# Watch1_1.net
KiCad netlist of a schematic drawn in EAGLE
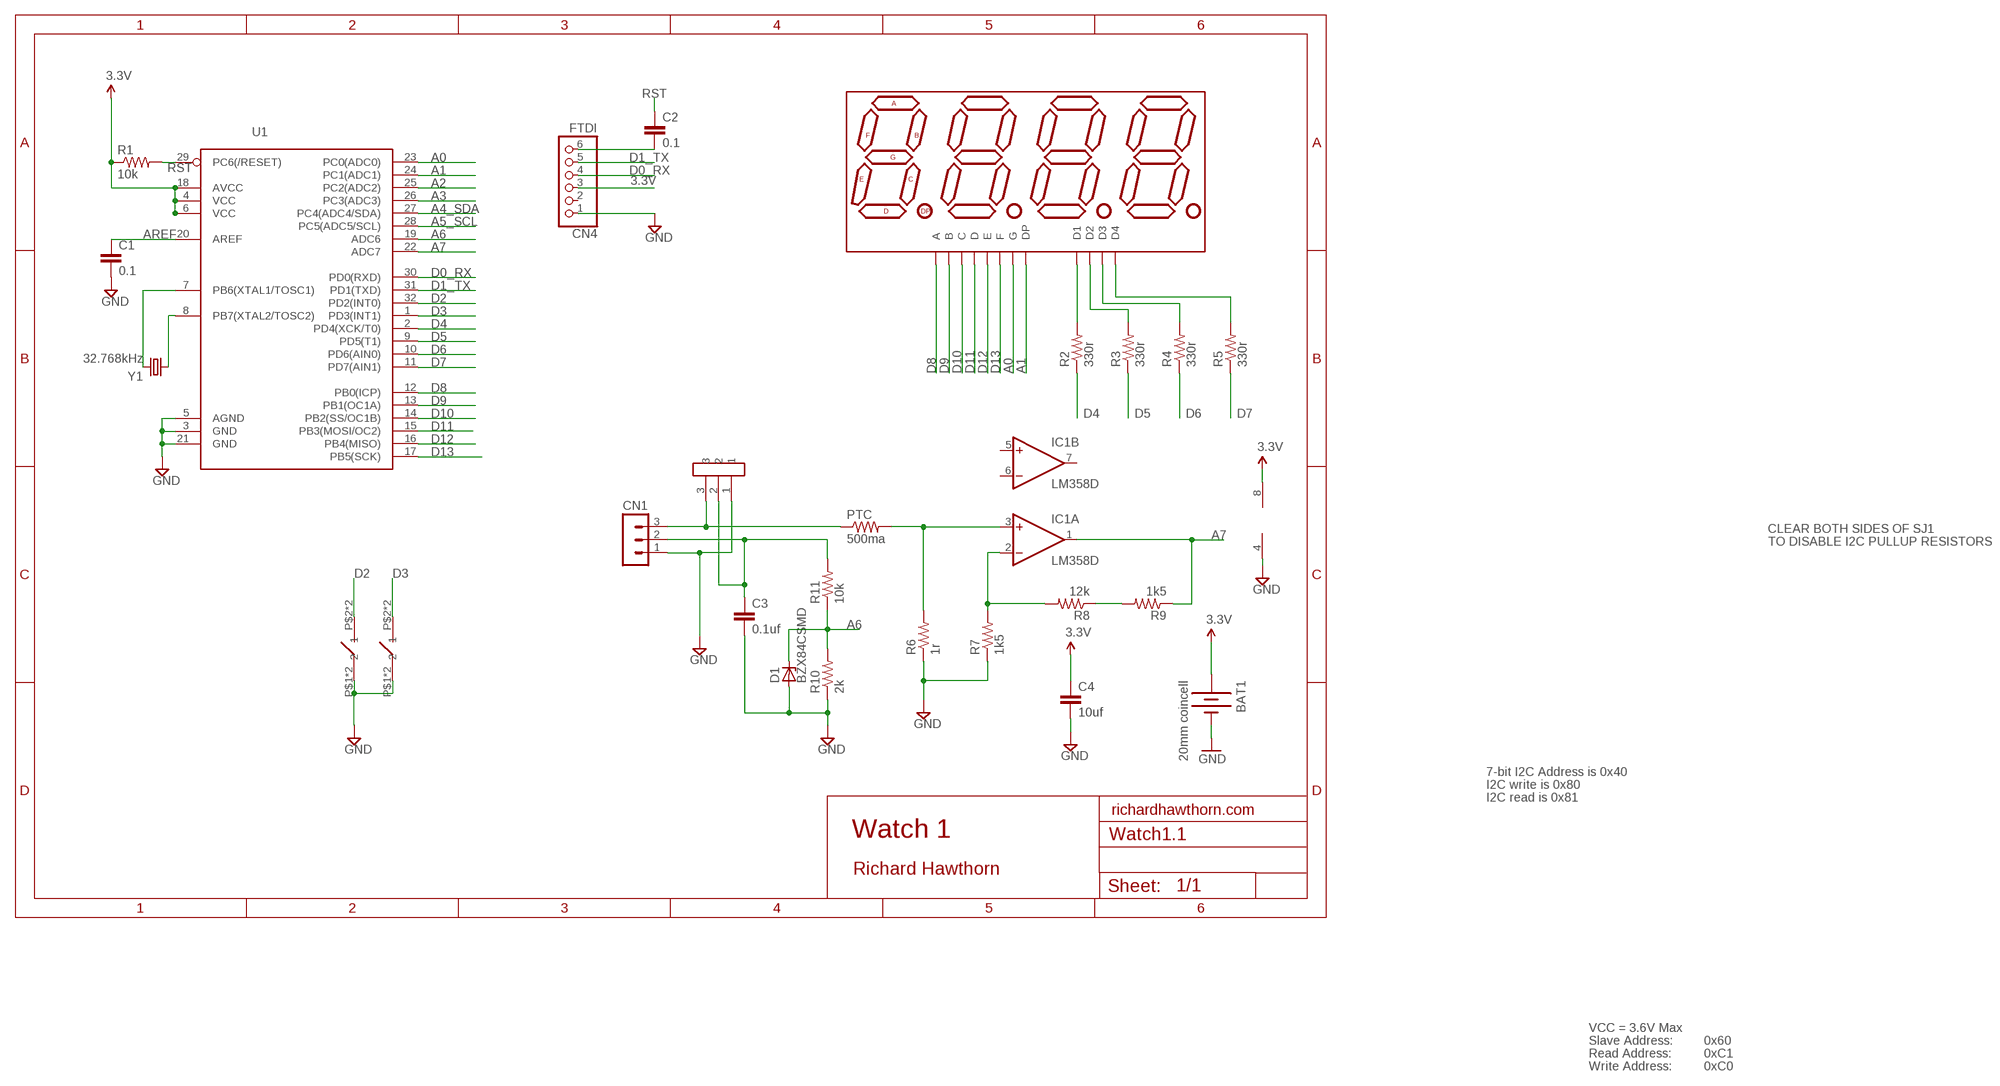
[diagram p0: schematic, sheet 1]

(export (version "E")
  (design (tool "Eeschema 10.0.6"))
  (components
    (comp (ref "BAT1")
      (value "20mm coincell")
      (footprint "eagle-import:BATTCON_20MM_4LEGS_OVERPASTE")
      (libsource (lib "eagle-import") (part "BATTERY20MM_4LEGS_OVERPASTE"))
    )
    (comp (ref "BTN1")
      (value "TURTLE-3PIN")
      (footprint "eagle-import:TURTLE-3PIN")
      (libsource (lib "eagle-import") (part "TURTLE-3PIN"))
    )
    (comp (ref "BTN2")
      (value "TURTLE-3PIN")
      (footprint "eagle-import:TURTLE-3PIN")
      (libsource (lib "eagle-import") (part "TURTLE-3PIN"))
    )
    (comp (ref "C1")
      (value "0.1")
      (footprint "eagle-import:0603-CAP")
      (libsource (lib "eagle-import") (part "CAP0603-CAP"))
    )
    (comp (ref "C2")
      (value "0.1")
      (footprint "eagle-import:0603-CAP")
      (libsource (lib "eagle-import") (part "CAP0603-CAP"))
    )
    (comp (ref "C3")
      (value "0.1uf")
      (footprint "eagle-import:0603-CAP")
      (libsource (lib "eagle-import") (part "CAP0603-CAP"))
    )
    (comp (ref "C4")
      (value "10uf")
      (footprint "eagle-import:0603-CAP")
      (libsource (lib "eagle-import") (part "CAP0603-CAP"))
    )
    (comp (ref "CN1")
      (value "MA03-1")
      (footprint "eagle-import:MA03-1")
      (libsource (lib "eagle-import") (part "MA03-1"))
    )
    (comp (ref "CN2")
      (value "3PIN-HEADER-RA")
      (footprint "eagle-import:3PIN_HEAD_RA")
      (libsource (lib "eagle-import") (part "3PIN-HEADER-RA"))
    )
    (comp (ref "CN4")
      (value "FTDI")
      (footprint "eagle-import:1X06")
      (libsource (lib "eagle-import") (part "PINHD-1X6"))
    )
    (comp (ref "D1")
      (value "BZX84CSMD")
      (footprint "eagle-import:TO236")
      (libsource (lib "eagle-import") (part "BZX84CSMD"))
    )
    (comp (ref "IC1")
      (value "LM358D")
      (footprint "eagle-import:SO08")
      (libsource (lib "eagle-import") (part "LM358D"))
    )
    (comp (ref "LED1")
      (value "HP_DISPLAY")
      (footprint "eagle-import:DIL12")
      (libsource (lib "eagle-import") (part "HP_DISPLAY"))
    )
    (comp (ref "PTC")
      (value "500ma")
      (footprint "eagle-import:R1206")
      (libsource (lib "eagle-import") (part "R-US_R1206"))
    )
    (comp (ref "R1")
      (value "10k")
      (footprint "eagle-import:0603-RES")
      (libsource (lib "eagle-import") (part "RESISTOR0603-RES"))
    )
    (comp (ref "R2")
      (value "330r")
      (footprint "eagle-import:0805")
      (libsource (lib "eagle-import") (part "RESISTOR0805"))
    )
    (comp (ref "R3")
      (value "330r")
      (footprint "eagle-import:0805")
      (libsource (lib "eagle-import") (part "RESISTOR0805"))
    )
    (comp (ref "R4")
      (value "330r")
      (footprint "eagle-import:0805")
      (libsource (lib "eagle-import") (part "RESISTOR0805"))
    )
    (comp (ref "R5")
      (value "330r")
      (footprint "eagle-import:0805")
      (libsource (lib "eagle-import") (part "RESISTOR0805"))
    )
    (comp (ref "R6")
      (value "1r")
      (footprint "eagle-import:0805")
      (libsource (lib "eagle-import") (part "RESISTOR0805"))
    )
    (comp (ref "R7")
      (value "1k5")
      (footprint "eagle-import:0805")
      (libsource (lib "eagle-import") (part "RESISTOR0805"))
    )
    (comp (ref "R8")
      (value "12k")
      (footprint "eagle-import:0805")
      (libsource (lib "eagle-import") (part "RESISTOR0805"))
    )
    (comp (ref "R9")
      (value "1k5")
      (footprint "eagle-import:0805")
      (libsource (lib "eagle-import") (part "RESISTOR0805"))
    )
    (comp (ref "R10")
      (value "2k")
      (footprint "eagle-import:0805")
      (libsource (lib "eagle-import") (part "RESISTOR0805"))
    )
    (comp (ref "R11")
      (value "10k")
      (footprint "eagle-import:0805")
      (libsource (lib "eagle-import") (part "RESISTOR0805"))
    )
    (comp (ref "U1")
      (value "ATMega-328")
      (footprint "eagle-import:TQFP32-08")
      (libsource (lib "eagle-import") (part "ATMEGA168/328TQFP32"))
    )
    (comp (ref "Y1")
      (value "32.768kHz")
      (footprint "eagle-import:TC26HEZ")
      (libsource (lib "eagle-import") (part "CRYSTALTC26H_EZ"))
    )
  )
  (nets
    (net (code "1") (name "/A0") (class "Default")
      (node (ref "LED1") (pin "7") (pinfunction "G_7") (pintype "bidirectional"))
      (node (ref "U1") (pin "23") (pinfunction "PC0(ADC0)_23") (pintype "bidirectional"))
    )
    (net (code "2") (name "/A1") (class "Default")
      (node (ref "LED1") (pin "5") (pinfunction "DP_5") (pintype "bidirectional"))
      (node (ref "U1") (pin "24") (pinfunction "PC1(ADC1)_24") (pintype "bidirectional"))
    )
    (net (code "3") (name "/A2") (class "Default")
      (node (ref "U1") (pin "25") (pinfunction "PC2(ADC2)_25") (pintype "bidirectional"))
    )
    (net (code "4") (name "/A3") (class "Default")
      (node (ref "U1") (pin "26") (pinfunction "PC3(ADC3)_26") (pintype "bidirectional"))
    )
    (net (code "5") (name "/A4_SDA") (class "Default")
      (node (ref "U1") (pin "27") (pinfunction "PC4(ADC4/SDA)_27") (pintype "bidirectional"))
    )
    (net (code "6") (name "/A5_SCL") (class "Default")
      (node (ref "U1") (pin "28") (pinfunction "PC5(ADC5/SCL)_28") (pintype "bidirectional"))
    )
    (net (code "7") (name "/A6") (class "Default")
      (node (ref "D1") (pin "C") (pinfunction "C_C") (pintype "passive"))
      (node (ref "R10") (pin "2") (pinfunction "2_2") (pintype "passive"))
      (node (ref "R11") (pin "1") (pinfunction "1_1") (pintype "passive"))
      (node (ref "U1") (pin "19") (pinfunction "ADC6_19") (pintype "bidirectional"))
    )
    (net (code "8") (name "/A7") (class "Default")
      (node (ref "IC1") (pin "1") (pinfunction "OUT_1") (pintype "output"))
      (node (ref "R9") (pin "1") (pinfunction "1_1") (pintype "passive"))
      (node (ref "U1") (pin "22") (pinfunction "ADC7_22") (pintype "bidirectional"))
    )
    (net (code "9") (name "/AREF") (class "Default")
      (node (ref "C1") (pin "1") (pinfunction "1_1") (pintype "passive"))
      (node (ref "U1") (pin "20") (pinfunction "AREF_20") (pintype "bidirectional"))
    )
    (net (code "10") (name "/D0_RX") (class "Default")
      (node (ref "CN4") (pin "4") (pinfunction "4_4") (pintype "passive"))
      (node (ref "U1") (pin "30") (pinfunction "PD0(RXD)_30") (pintype "bidirectional"))
    )
    (net (code "11") (name "/D1_TX") (class "Default")
      (node (ref "CN4") (pin "5") (pinfunction "5_5") (pintype "passive"))
      (node (ref "U1") (pin "31") (pinfunction "PD1(TXD)_31") (pintype "bidirectional"))
    )
    (net (code "12") (name "/D2") (class "Default")
      (node (ref "BTN1") (pin "P$2") (pinfunction "2_P$2") (pintype "bidirectional"))
      (node (ref "BTN1") (pin "P$4") (pinfunction "2_P$4") (pintype "bidirectional"))
      (node (ref "U1") (pin "32") (pinfunction "PD2(INT0)_32") (pintype "bidirectional"))
    )
    (net (code "13") (name "/D3") (class "Default")
      (node (ref "BTN2") (pin "P$2") (pinfunction "2_P$2") (pintype "bidirectional"))
      (node (ref "BTN2") (pin "P$4") (pinfunction "2_P$4") (pintype "bidirectional"))
      (node (ref "U1") (pin "1") (pinfunction "PD3(INT1)_1") (pintype "bidirectional"))
    )
    (net (code "14") (name "/D4") (class "Default")
      (node (ref "R2") (pin "1") (pinfunction "1_1") (pintype "passive"))
      (node (ref "U1") (pin "2") (pinfunction "PD4(XCK/T0)_2") (pintype "bidirectional"))
    )
    (net (code "15") (name "/D5") (class "Default")
      (node (ref "R3") (pin "1") (pinfunction "1_1") (pintype "passive"))
      (node (ref "U1") (pin "9") (pinfunction "PD5(T1)_9") (pintype "bidirectional"))
    )
    (net (code "16") (name "/D6") (class "Default")
      (node (ref "R4") (pin "1") (pinfunction "1_1") (pintype "passive"))
      (node (ref "U1") (pin "10") (pinfunction "PD6(AIN0)_10") (pintype "bidirectional"))
    )
    (net (code "17") (name "/D7") (class "Default")
      (node (ref "R5") (pin "1") (pinfunction "1_1") (pintype "passive"))
      (node (ref "U1") (pin "11") (pinfunction "PD7(AIN1)_11") (pintype "bidirectional"))
    )
    (net (code "18") (name "/D8") (class "Default")
      (node (ref "LED1") (pin "12") (pinfunction "A_12") (pintype "bidirectional"))
      (node (ref "U1") (pin "12") (pinfunction "PB0(ICP)_12") (pintype "bidirectional"))
    )
    (net (code "19") (name "/D9") (class "Default")
      (node (ref "LED1") (pin "11") (pinfunction "B_11") (pintype "bidirectional"))
      (node (ref "U1") (pin "13") (pinfunction "PB1(OC1A)_13") (pintype "bidirectional"))
    )
    (net (code "20") (name "/D10") (class "Default")
      (node (ref "LED1") (pin "3") (pinfunction "C_3") (pintype "bidirectional"))
      (node (ref "U1") (pin "14") (pinfunction "PB2(SS/OC1B)_14") (pintype "bidirectional"))
    )
    (net (code "21") (name "/D11") (class "Default")
      (node (ref "LED1") (pin "8") (pinfunction "D_8") (pintype "bidirectional"))
      (node (ref "U1") (pin "15") (pinfunction "PB3(MOSI/OC2)_15") (pintype "bidirectional"))
    )
    (net (code "22") (name "/D12") (class "Default")
      (node (ref "LED1") (pin "2") (pinfunction "E_2") (pintype "bidirectional"))
      (node (ref "U1") (pin "16") (pinfunction "PB4(MISO)_16") (pintype "bidirectional"))
    )
    (net (code "23") (name "/D13") (class "Default")
      (node (ref "LED1") (pin "9") (pinfunction "F_9") (pintype "bidirectional"))
      (node (ref "U1") (pin "17") (pinfunction "PB5(SCK)_17") (pintype "bidirectional"))
    )
    (net (code "24") (name "/RST") (class "Default")
      (node (ref "C2") (pin "1") (pinfunction "1_1") (pintype "passive"))
      (node (ref "R1") (pin "2") (pinfunction "2_2") (pintype "passive"))
      (node (ref "U1") (pin "29") (pinfunction "PC6(/RESET)_29") (pintype "bidirectional"))
    )
    (net (code "25") (name "3.3V") (class "Default")
      (node (ref "BAT1") (pin "1") (pinfunction "+_1") (pintype "power_in"))
      (node (ref "C4") (pin "1") (pinfunction "1_1") (pintype "passive"))
      (node (ref "CN4") (pin "3") (pinfunction "3_3") (pintype "passive"))
      (node (ref "IC1") (pin "8") (pinfunction "V+_8") (pintype "power_in"))
      (node (ref "R1") (pin "1") (pinfunction "1_1") (pintype "passive"))
      (node (ref "U1") (pin "18") (pinfunction "AVCC_18") (pintype "bidirectional"))
      (node (ref "U1") (pin "4") (pinfunction "VCC_4") (pintype "bidirectional"))
      (node (ref "U1") (pin "6") (pinfunction "VCC_6") (pintype "bidirectional"))
    )
    (net (code "26") (name "GND") (class "Default")
      (node (ref "BAT1") (pin "2") (pinfunction "-_2") (pintype "power_in"))
      (node (ref "BTN1") (pin "P$1") (pinfunction "1_P$1") (pintype "bidirectional"))
      (node (ref "BTN1") (pin "P$3") (pinfunction "1_P$3") (pintype "bidirectional"))
      (node (ref "BTN2") (pin "P$1") (pinfunction "1_P$1") (pintype "bidirectional"))
      (node (ref "BTN2") (pin "P$3") (pinfunction "1_P$3") (pintype "bidirectional"))
      (node (ref "C1") (pin "2") (pinfunction "2_2") (pintype "passive"))
      (node (ref "C3") (pin "2") (pinfunction "2_2") (pintype "passive"))
      (node (ref "C4") (pin "2") (pinfunction "2_2") (pintype "passive"))
      (node (ref "CN1") (pin "1") (pinfunction "1_1") (pintype "passive"))
      (node (ref "CN2") (pin "1") (pinfunction "1_1") (pintype "bidirectional"))
      (node (ref "CN4") (pin "1") (pinfunction "1_1") (pintype "passive"))
      (node (ref "D1") (pin "A") (pinfunction "A_A") (pintype "passive"))
      (node (ref "IC1") (pin "4") (pinfunction "V-_4") (pintype "power_in"))
      (node (ref "R10") (pin "1") (pinfunction "1_1") (pintype "passive"))
      (node (ref "R6") (pin "1") (pinfunction "1_1") (pintype "passive"))
      (node (ref "R7") (pin "1") (pinfunction "1_1") (pintype "passive"))
      (node (ref "U1") (pin "21") (pinfunction "GND_21") (pintype "bidirectional"))
      (node (ref "U1") (pin "3") (pinfunction "GND_3") (pintype "bidirectional"))
      (node (ref "U1") (pin "5") (pinfunction "AGND_5") (pintype "bidirectional"))
    )
    (net (code "27") (name "Net-(C2-Pad2)") (class "Default")
      (node (ref "C2") (pin "2") (pinfunction "2_2") (pintype "passive"))
      (node (ref "CN4") (pin "6") (pinfunction "6_6") (pintype "passive"))
    )
    (net (code "28") (name "Net-(C3-Pad1)") (class "Default")
      (node (ref "C3") (pin "1") (pinfunction "1_1") (pintype "passive"))
      (node (ref "CN1") (pin "2") (pinfunction "2_2") (pintype "passive"))
      (node (ref "CN2") (pin "2") (pinfunction "2_2") (pintype "bidirectional"))
      (node (ref "R11") (pin "2") (pinfunction "2_2") (pintype "passive"))
    )
    (net (code "29") (name "Net-(CN1-Pad3)") (class "Default")
      (node (ref "CN1") (pin "3") (pinfunction "3_3") (pintype "passive"))
      (node (ref "CN2") (pin "3") (pinfunction "3_3") (pintype "bidirectional"))
      (node (ref "PTC") (pin "1") (pinfunction "1_1") (pintype "passive"))
    )
    (net (code "30") (name "Net-(IC1A-+IN)") (class "Default")
      (node (ref "IC1") (pin "3") (pinfunction "+IN_3") (pintype "input"))
      (node (ref "PTC") (pin "2") (pinfunction "2_2") (pintype "passive"))
      (node (ref "R6") (pin "2") (pinfunction "2_2") (pintype "passive"))
    )
    (net (code "31") (name "Net-(IC1A--IN)") (class "Default")
      (node (ref "IC1") (pin "2") (pinfunction "-IN_2") (pintype "input"))
      (node (ref "R7") (pin "2") (pinfunction "2_2") (pintype "passive"))
      (node (ref "R8") (pin "2") (pinfunction "2_2") (pintype "passive"))
    )
    (net (code "32") (name "Net-(LED1-D1)") (class "Default")
      (node (ref "LED1") (pin "1") (pinfunction "D1_1") (pintype "bidirectional"))
      (node (ref "R2") (pin "2") (pinfunction "2_2") (pintype "passive"))
    )
    (net (code "33") (name "Net-(LED1-D2)") (class "Default")
      (node (ref "LED1") (pin "10") (pinfunction "D2_10") (pintype "bidirectional"))
      (node (ref "R3") (pin "2") (pinfunction "2_2") (pintype "passive"))
    )
    (net (code "34") (name "Net-(LED1-D3)") (class "Default")
      (node (ref "LED1") (pin "4") (pinfunction "D3_4") (pintype "bidirectional"))
      (node (ref "R4") (pin "2") (pinfunction "2_2") (pintype "passive"))
    )
    (net (code "35") (name "Net-(LED1-D4)") (class "Default")
      (node (ref "LED1") (pin "6") (pinfunction "D4_6") (pintype "bidirectional"))
      (node (ref "R5") (pin "2") (pinfunction "2_2") (pintype "passive"))
    )
    (net (code "36") (name "Net-(R8-Pad1)") (class "Default")
      (node (ref "R8") (pin "1") (pinfunction "1_1") (pintype "passive"))
      (node (ref "R9") (pin "2") (pinfunction "2_2") (pintype "passive"))
    )
    (net (code "37") (name "Net-(U1-PB6(XTAL1{slash}TOSC1))") (class "Default")
      (node (ref "U1") (pin "7") (pinfunction "PB6(XTAL1/TOSC1)_7") (pintype "bidirectional"))
      (node (ref "Y1") (pin "2") (pinfunction "2_2") (pintype "passive"))
    )
    (net (code "38") (name "Net-(U1-PB7(XTAL2{slash}TOSC2))") (class "Default")
      (node (ref "U1") (pin "8") (pinfunction "PB7(XTAL2/TOSC2)_8") (pintype "bidirectional"))
      (node (ref "Y1") (pin "1") (pinfunction "1_1") (pintype "passive"))
    )
    (net (code "39") (name "unconnected-(CN4-Pad2)") (class "Default")
      (node (ref "CN4") (pin "2") (pinfunction "2_2") (pintype "passive"))
    )
    (net (code "40") (name "unconnected-(IC1B-+IN-Pad5)") (class "Default")
      (node (ref "IC1") (pin "5") (pinfunction "+IN_5") (pintype "input"))
    )
    (net (code "41") (name "unconnected-(IC1B--IN-Pad6)") (class "Default")
      (node (ref "IC1") (pin "6") (pinfunction "-IN_6") (pintype "input"))
    )
    (net (code "42") (name "unconnected-(IC1B-OUT-Pad7)") (class "Default")
      (node (ref "IC1") (pin "7") (pinfunction "OUT_7") (pintype "output"))
    )
  )
)
